# L_gendetektor.net
KiCad netlist of a schematic drawn in EAGLE
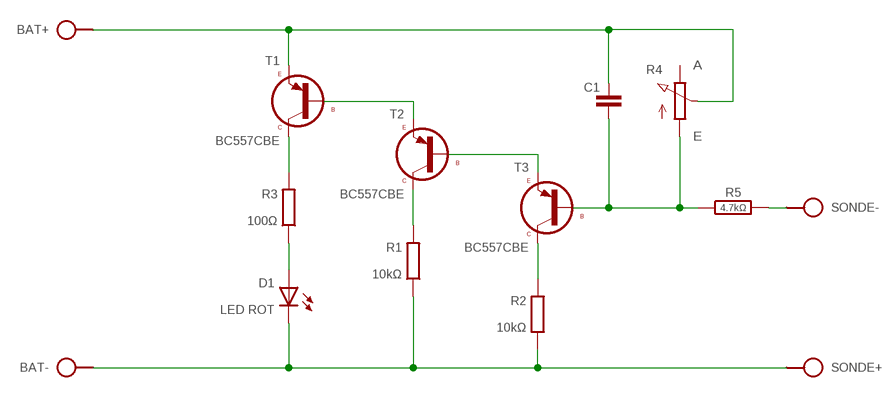
[diagram p0: schematic, sheet 1]

(export (version "E")
  (design (tool "Eeschema 10.0.6"))
  (components
    (comp (ref "BAT")
      (value "SPAD+-+-")
      (footprint "eagle-import:SPAD+-")
      (libsource (lib "eagle-import") (part "SPAD+-+-"))
    )
    (comp (ref "C1")
      (value "C050-020X044/V")
      (footprint "eagle-import:C050-020X044_V")
      (libsource (lib "eagle-import") (part "C050-020X044/V"))
    )
    (comp (ref "D1")
      (value "LED ROT")
      (footprint "eagle-import:LED_3MM_V")
      (libsource (lib "eagle-import") (part "LED-3MM/V"))
    )
    (comp (ref "R1")
      (value "10kΩ")
      (footprint "eagle-import:0204_10-V")
      (libsource (lib "eagle-import") (part "R0204/10-V"))
    )
    (comp (ref "R2")
      (value "10kΩ")
      (footprint "eagle-import:0204_10-V")
      (libsource (lib "eagle-import") (part "R0204/10-V"))
    )
    (comp (ref "R3")
      (value "100Ω")
      (footprint "eagle-import:0204_10-V")
      (libsource (lib "eagle-import") (part "R0204/10-V"))
    )
    (comp (ref "R4")
      (value "POT-V")
      (footprint "eagle-import:POT-V")
      (libsource (lib "eagle-import") (part "POT-V"))
    )
    (comp (ref "R5")
      (value "4.7kΩ")
      (footprint "eagle-import:0204_10")
      (libsource (lib "eagle-import") (part "R-H0204/10"))
    )
    (comp (ref "SONDE")
      (value "SPAD+-+-")
      (footprint "eagle-import:SPAD+-")
      (libsource (lib "eagle-import") (part "SPAD+-+-"))
    )
    (comp (ref "T1")
      (value "BC557CBE")
      (footprint "eagle-import:TO92-CBE")
      (libsource (lib "eagle-import") (part "BC557CBE"))
    )
    (comp (ref "T2")
      (value "BC557CBE")
      (footprint "eagle-import:TO92-CBE")
      (libsource (lib "eagle-import") (part "BC557CBE"))
    )
    (comp (ref "T3")
      (value "BC557CBE")
      (footprint "eagle-import:TO92-CBE")
      (libsource (lib "eagle-import") (part "BC557CBE"))
    )
  )
  (nets
    (net (code "1") (name "Net-(BATA-P$1)") (class "Default")
      (node (ref "BAT") (pin "2") (pinfunction "P$1_2") (pintype "passive"))
      (node (ref "C1") (pin "1") (pinfunction "1_1") (pintype "passive"))
      (node (ref "R4") (pin "S") (pinfunction "S_S") (pintype "passive"))
      (node (ref "T1") (pin "3") (pinfunction "E_3") (pintype "passive"))
    )
    (net (code "2") (name "Net-(BATB-P$1)") (class "Default")
      (node (ref "BAT") (pin "1") (pinfunction "P$1_1") (pintype "passive"))
      (node (ref "D1") (pin "K") (pinfunction "C_K") (pintype "passive"))
      (node (ref "R1") (pin "2") (pinfunction "1_2") (pintype "passive"))
      (node (ref "R2") (pin "2") (pinfunction "1_2") (pintype "passive"))
      (node (ref "SONDE") (pin "2") (pinfunction "P$1_2") (pintype "passive"))
    )
    (net (code "3") (name "Net-(R1-2)") (class "Default")
      (node (ref "R1") (pin "1") (pinfunction "2_1") (pintype "passive"))
      (node (ref "T2") (pin "1") (pinfunction "C_1") (pintype "passive"))
    )
    (net (code "4") (name "Net-(R2-2)") (class "Default")
      (node (ref "R2") (pin "1") (pinfunction "2_1") (pintype "passive"))
      (node (ref "T3") (pin "1") (pinfunction "C_1") (pintype "passive"))
    )
    (net (code "5") (name "Net-(R3-1)") (class "Default")
      (node (ref "D1") (pin "A") (pinfunction "A_A") (pintype "passive"))
      (node (ref "R3") (pin "2") (pinfunction "1_2") (pintype "passive"))
    )
    (net (code "6") (name "Net-(R3-2)") (class "Default")
      (node (ref "R3") (pin "1") (pinfunction "2_1") (pintype "passive"))
      (node (ref "T1") (pin "1") (pinfunction "C_1") (pintype "passive"))
    )
    (net (code "7") (name "Net-(SONDEB-P$1)") (class "Default")
      (node (ref "R5") (pin "2") (pinfunction "2_2") (pintype "passive"))
      (node (ref "SONDE") (pin "1") (pinfunction "P$1_1") (pintype "passive"))
    )
    (net (code "8") (name "Net-(T1-B)") (class "Default")
      (node (ref "T1") (pin "2") (pinfunction "B_2") (pintype "passive"))
      (node (ref "T2") (pin "3") (pinfunction "E_3") (pintype "passive"))
    )
    (net (code "9") (name "Net-(T2-B)") (class "Default")
      (node (ref "T2") (pin "2") (pinfunction "B_2") (pintype "passive"))
      (node (ref "T3") (pin "3") (pinfunction "E_3") (pintype "passive"))
    )
    (net (code "10") (name "Net-(T3-B)") (class "Default")
      (node (ref "C1") (pin "2") (pinfunction "2_2") (pintype "passive"))
      (node (ref "R4") (pin "A") (pinfunction "A_A") (pintype "passive"))
      (node (ref "R5") (pin "1") (pinfunction "1_1") (pintype "passive"))
      (node (ref "T3") (pin "2") (pinfunction "B_2") (pintype "passive"))
    )
    (net (code "11") (name "unconnected-(R4-PadE)") (class "Default")
      (node (ref "R4") (pin "E") (pinfunction "E_E") (pintype "passive"))
    )
  )
)
